# FET.net
KiCad netlist of a schematic drawn in Altium Designer
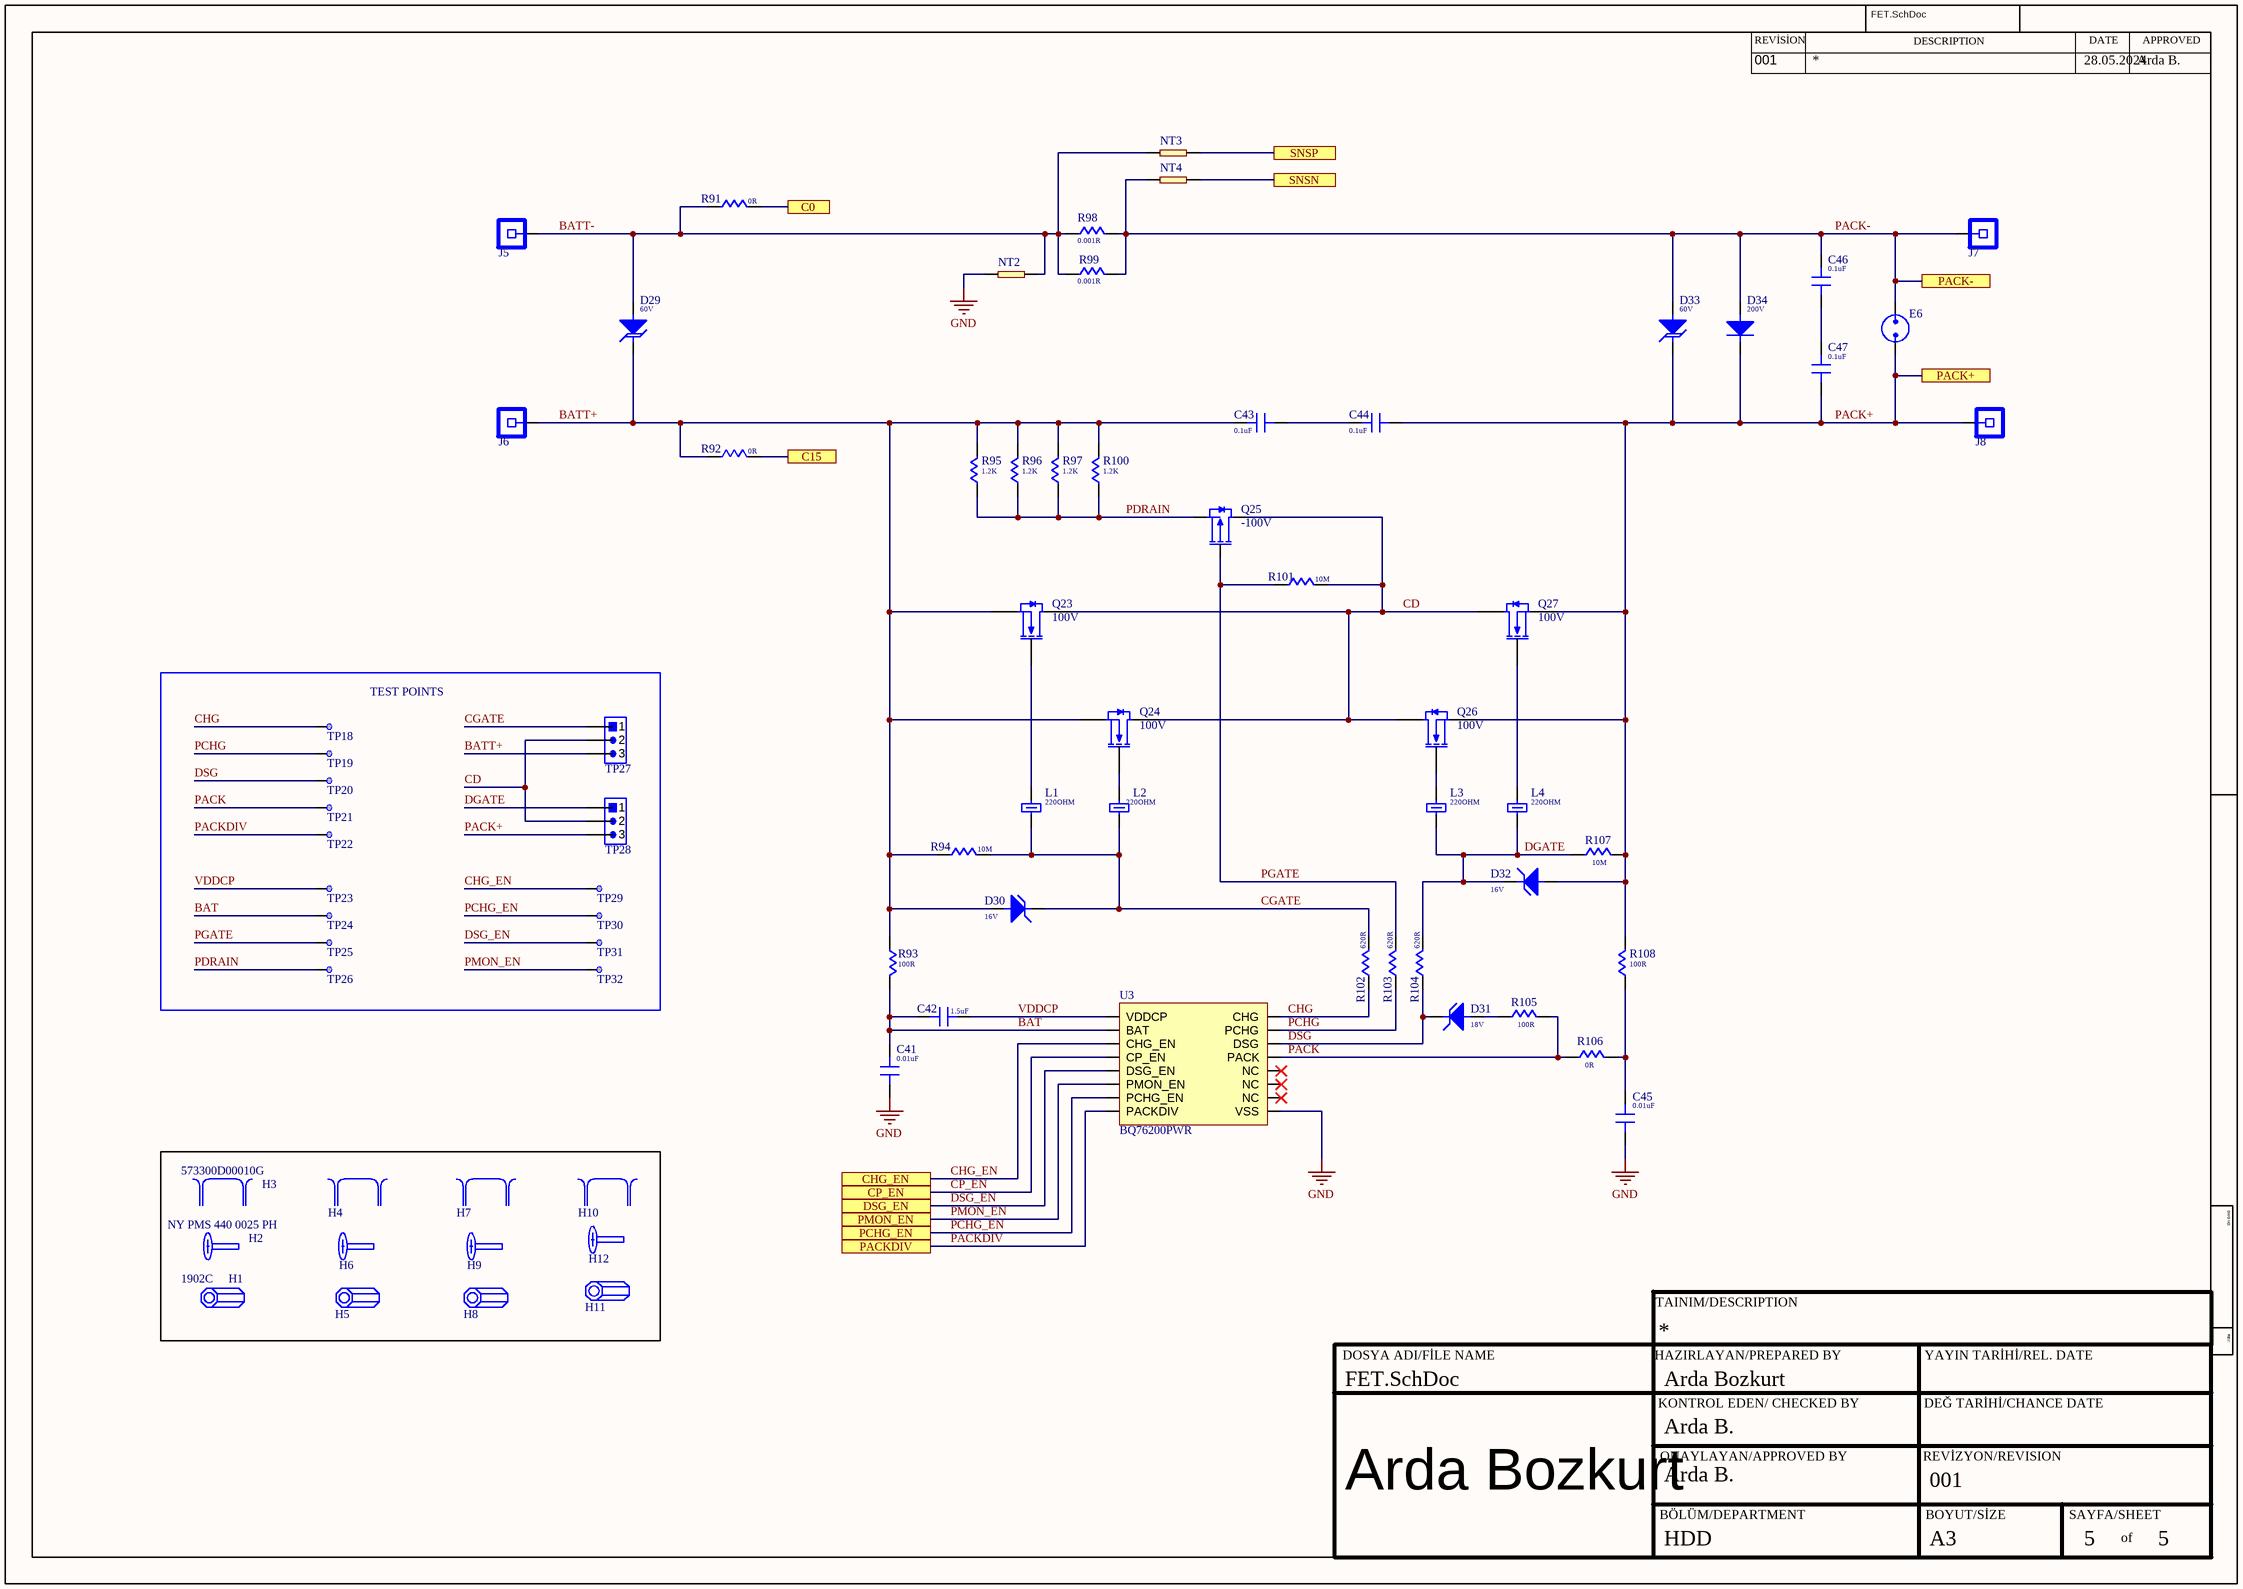
[diagram p0: FET.SchDoc]

(export (version "E")
  (design (tool "Eeschema 10.0.6"))
  (components
    (comp (ref "C41")
      (value "0.01uF")
      (footprint "C_0805")
      (description "Cap Cer 10000PF 100V X7R 0805")
      (fields
        (field (name "MANUFACTURER") "Kyocera AVX")
        (field (name "MANUFACTURER PART NUMBER") "KGM21NR72A103KT")
      )
      (libsource (lib "BMS_Lib") (part "C_0.01uF_0805_100V"))
    )
    (comp (ref "C42")
      (value "1.5uF")
      (footprint "C_0805")
      (description "0805 1.5 uF 25 V ±10% Tolerance X7R SMT Multilayer Ceramic Capacitor")
      (fields
        (field (name "MANUFACTURER") "Murata")
        (field (name "MANUFACTURER PART NUMBER") "GRM21BR71E155KA88L")
      )
      (libsource (lib "BMS_Lib") (part "C_1.5uF_0805_25V"))
    )
    (comp (ref "C43")
      (value "0.1uF")
      (footprint "C_0603")
      (description "Multilayer Ceramic Capacitor, 0.1 uF, 100 V, ± 10%, X7R, 0603 [1608 Metric]")
      (fields
        (field (name "MANUFACTURER") "Murata")
        (field (name "MANUFACTURER PART NUMBER") "GRM188R72A104KA35D")
      )
      (libsource (lib "BMS_Lib") (part "C_0.1uF_0603_100V"))
    )
    (comp (ref "C44")
      (value "0.1uF")
      (footprint "C_0603")
      (description "Multilayer Ceramic Capacitor, 0.1 uF, 100 V, ± 10%, X7R, 0603 [1608 Metric]")
      (fields
        (field (name "MANUFACTURER") "Murata")
        (field (name "MANUFACTURER PART NUMBER") "GRM188R72A104KA35D")
      )
      (libsource (lib "BMS_Lib") (part "C_0.1uF_0603_100V"))
    )
    (comp (ref "C45")
      (value "0.01uF")
      (footprint "C_0805")
      (description "Cap Cer 10000PF 100V X7R 0805")
      (fields
        (field (name "MANUFACTURER") "Kyocera AVX")
        (field (name "MANUFACTURER PART NUMBER") "KGM21NR72A103KT")
      )
      (libsource (lib "BMS_Lib") (part "C_0.01uF_0805_100V"))
    )
    (comp (ref "C46")
      (value "0.1uF")
      (footprint "C_0603")
      (description "Multilayer Ceramic Capacitor, 0.1 uF, 100 V, ± 10%, X7R, 0603 [1608 Metric]")
      (fields
        (field (name "MANUFACTURER") "Murata")
        (field (name "MANUFACTURER PART NUMBER") "GRM188R72A104KA35D")
      )
      (libsource (lib "BMS_Lib") (part "C_0.1uF_0603_100V"))
    )
    (comp (ref "C47")
      (value "0.1uF")
      (footprint "C_0603")
      (description "Multilayer Ceramic Capacitor, 0.1 uF, 100 V, ± 10%, X7R, 0603 [1608 Metric]")
      (fields
        (field (name "MANUFACTURER") "Murata")
        (field (name "MANUFACTURER PART NUMBER") "GRM188R72A104KA35D")
      )
      (libsource (lib "BMS_Lib") (part "C_0.1uF_0603_100V"))
    )
    (comp (ref "D29")
      (value "60V")
      (footprint "D_SMC")
      (description "Diode TVS Single Uni-Dir 6V 1.5KW 2-Pin DO-214AB")
      (fields (field (name "MANUFACTURER") "Littelfuse") (field (name "MANUFACTURER PART NUMBER") "SMCJ6.0A"))
      (libsource (lib "BMS_Lib") (part "D_TVS_60V-SMC"))
    )
    (comp (ref "D30")
      (value "16V")
      (footprint "D_SOD323")
      (description "Zener Diode, 16V, 0.2W, Sod-323 Rohs Compliant: Yes ¦Diodes Inc. MMSZ5246BS-7-F")
      (fields
        (field (name "MANUFACTURER") "Diodes Zetex")
        (field (name "MANUFACTURER PART NUMBER") "MMSZ5246BS-7-F")
      )
      (libsource (lib "BMS_Lib") (part "D_ZENER_16V_SOD323"))
    )
    (comp (ref "D31")
      (value "18V")
      (footprint "D_SOD323")
      (description "Diode Zener Single 18V 5% 200mW Automotive 2-Pin SOD-323 T/R")
      (fields
        (field (name "MANUFACTURER") "Diodes")
        (field (name "MANUFACTURER PART NUMBER") "MMSZ5248BS-7-F")
      )
      (libsource (lib "BMS_Lib") (part "D_ZENER_18V_SOD323"))
    )
    (comp (ref "D32")
      (value "16V")
      (footprint "D_SOD323")
      (description "Zener Diode, 16V, 0.2W, Sod-323 Rohs Compliant: Yes ¦Diodes Inc. MMSZ5246BS-7-F")
      (fields
        (field (name "MANUFACTURER") "Diodes Zetex")
        (field (name "MANUFACTURER PART NUMBER") "MMSZ5246BS-7-F")
      )
      (libsource (lib "BMS_Lib") (part "D_ZENER_16V_SOD323"))
    )
    (comp (ref "D33")
      (value "60V")
      (footprint "D_SMC")
      (description "Diode TVS Single Uni-Dir 6V 1.5KW 2-Pin DO-214AB")
      (fields (field (name "MANUFACTURER") "Littelfuse") (field (name "MANUFACTURER PART NUMBER") "SMCJ6.0A"))
      (libsource (lib "BMS_Lib") (part "D_TVS_60V-SMC"))
    )
    (comp (ref "D34")
      (value "200V")
      (footprint "D_DO214AB")
      (description "Rectifier Diode Switching 200V 3A 20ns 2-Pin SMC T/R / DIODE GEN PURP 200V 3A DO214AB")
      (fields
        (field (name "MANUFACTURER") "Vishay Semiconductors")
        (field (name "MANUFACTURER PART NUMBER") "ES3D-E3/57T")
      )
      (libsource (lib "BMS_Lib") (part "D_GENPURP_200V_DO214AB"))
    )
    (comp (ref "E6")
      (value "SPARKGAP")
      (footprint "SPARK_GARP")
      (description "Spark Gap")
      (libsource (lib "BMS_Lib") (part "E_Spark_Gap"))
    )
    (comp (ref "H1")
      (value "1902C")
      (footprint "HEX_STANDOFF")
      (description "Transistor: 2xN-MOSFET; unipolar; 20V; 1.1A; 0.235ohm; 420mW; -55+150 deg.C; SMD; SC70-6")
      (fields
        (field (name "MANUFACTURER") "Vishay")
        (field (name "MANUFACTURER PART NUMBER") "SI1902CDL-T1-GE3")
      )
      (libsource (lib "BMS_Lib") (part "HEX STANDOFF"))
    )
    (comp (ref "H2")
      (value "NY PMS 440 0025 PH")
      (footprint "PEN")
      (description "Machine Screw Pan Phillips 4-40")
      (fields (field (name "MANUFACTURER") "Building Fasteners"))
      (libsource (lib "BMS_Lib") (part "MACHINE SCREW PAN PHILLIPS 4-40"))
    )
    (comp (ref "H3")
      (value "573300D00010G")
      (footprint "HEATSINK")
      (description "TO-226 Surface Mount 18.00 C/W Thermal Resistance D2 Semiconductor Heat Sink")
      (fields (field (name "MANUFACTURER") "Aavid Thermalloy"))
      (libsource (lib "BMS_Lib") (part "Heatsink"))
    )
    (comp (ref "H4")
      (value "573300D00010G")
      (footprint "HEATSINK")
      (description "TO-226 Surface Mount 18.00 C/W Thermal Resistance D2 Semiconductor Heat Sink")
      (fields (field (name "MANUFACTURER") "Aavid Thermalloy"))
      (libsource (lib "BMS_Lib") (part "Heatsink"))
    )
    (comp (ref "H5")
      (value "1902C")
      (footprint "HEX_STANDOFF")
      (description "Transistor: 2xN-MOSFET; unipolar; 20V; 1.1A; 0.235ohm; 420mW; -55+150 deg.C; SMD; SC70-6")
      (fields
        (field (name "MANUFACTURER") "Vishay")
        (field (name "MANUFACTURER PART NUMBER") "SI1902CDL-T1-GE3")
      )
      (libsource (lib "BMS_Lib") (part "HEX STANDOFF"))
    )
    (comp (ref "H6")
      (value "NY PMS 440 0025 PH")
      (footprint "PEN")
      (description "Machine Screw Pan Phillips 4-40")
      (fields (field (name "MANUFACTURER") "Building Fasteners"))
      (libsource (lib "BMS_Lib") (part "MACHINE SCREW PAN PHILLIPS 4-40"))
    )
    (comp (ref "H7")
      (value "573300D00010G")
      (footprint "HEATSINK")
      (description "TO-226 Surface Mount 18.00 C/W Thermal Resistance D2 Semiconductor Heat Sink")
      (fields (field (name "MANUFACTURER") "Aavid Thermalloy"))
      (libsource (lib "BMS_Lib") (part "Heatsink"))
    )
    (comp (ref "H8")
      (value "1902C")
      (footprint "HEX_STANDOFF")
      (description "Transistor: 2xN-MOSFET; unipolar; 20V; 1.1A; 0.235ohm; 420mW; -55+150 deg.C; SMD; SC70-6")
      (fields
        (field (name "MANUFACTURER") "Vishay")
        (field (name "MANUFACTURER PART NUMBER") "SI1902CDL-T1-GE3")
      )
      (libsource (lib "BMS_Lib") (part "HEX STANDOFF"))
    )
    (comp (ref "H9")
      (value "NY PMS 440 0025 PH")
      (footprint "PEN")
      (description "Machine Screw Pan Phillips 4-40")
      (fields (field (name "MANUFACTURER") "Building Fasteners"))
      (libsource (lib "BMS_Lib") (part "MACHINE SCREW PAN PHILLIPS 4-40"))
    )
    (comp (ref "H10")
      (value "573300D00010G")
      (footprint "HEATSINK")
      (description "TO-226 Surface Mount 18.00 C/W Thermal Resistance D2 Semiconductor Heat Sink")
      (fields (field (name "MANUFACTURER") "Aavid Thermalloy"))
      (libsource (lib "BMS_Lib") (part "Heatsink"))
    )
    (comp (ref "H11")
      (value "1902C")
      (footprint "HEX_STANDOFF")
      (description "Transistor: 2xN-MOSFET; unipolar; 20V; 1.1A; 0.235ohm; 420mW; -55+150 deg.C; SMD; SC70-6")
      (fields
        (field (name "MANUFACTURER") "Vishay")
        (field (name "MANUFACTURER PART NUMBER") "SI1902CDL-T1-GE3")
      )
      (libsource (lib "BMS_Lib") (part "HEX STANDOFF"))
    )
    (comp (ref "H12")
      (value "NY PMS 440 0025 PH")
      (footprint "PEN")
      (description "Machine Screw Pan Phillips 4-40")
      (fields (field (name "MANUFACTURER") "Building Fasteners"))
      (libsource (lib "BMS_Lib") (part "MACHINE SCREW PAN PHILLIPS 4-40"))
    )
    (comp (ref "J5")
      (value "ML4-CY")
      (footprint "CONN_LUG")
      (description "One-hole copper single barrel post lug straight tongue 14 SOL - 4 STR 1/4 (6.4mm) stud hole.")
      (fields (field (name "MANUFACTURER") "Panduit"))
      (libsource (lib "BMS_Lib") (part "CONN_LUG"))
    )
    (comp (ref "J6")
      (value "ML4-CY")
      (footprint "CONN_LUG")
      (description "One-hole copper single barrel post lug straight tongue 14 SOL - 4 STR 1/4 (6.4mm) stud hole.")
      (fields (field (name "MANUFACTURER") "Panduit"))
      (libsource (lib "BMS_Lib") (part "CONN_LUG"))
    )
    (comp (ref "J7")
      (value "ML4-CY")
      (footprint "CONN_LUG")
      (description "One-hole copper single barrel post lug straight tongue 14 SOL - 4 STR 1/4 (6.4mm) stud hole.")
      (fields (field (name "MANUFACTURER") "Panduit"))
      (libsource (lib "") (part "CONN_LUG_1"))
    )
    (comp (ref "J8")
      (value "ML4-CY")
      (footprint "CONN_LUG")
      (description "One-hole copper single barrel post lug straight tongue 14 SOL - 4 STR 1/4 (6.4mm) stud hole.")
      (fields (field (name "MANUFACTURER") "Panduit"))
      (libsource (lib "") (part "CONN_LUG_1"))
    )
    (comp (ref "L1")
      (value "220OHM")
      (footprint "L_0603")
      (description "Ferrite Beads Multi-Layer 220Ohm 25% 100MHz 2.5A 40mOhm DCR 0603 Paper T/R")
      (fields
        (field (name "MANUFACTURER") "Murata")
        (field (name "MANUFACTURER PART NUMBER") "BLM18SG221TN1D")
      )
      (libsource (lib "BMS_Lib") (part "L_FB_220OHM_0603"))
    )
    (comp (ref "L2")
      (value "220OHM")
      (footprint "L_0603")
      (description "Ferrite Beads Multi-Layer 220Ohm 25% 100MHz 2.5A 40mOhm DCR 0603 Paper T/R")
      (fields
        (field (name "MANUFACTURER") "Murata")
        (field (name "MANUFACTURER PART NUMBER") "BLM18SG221TN1D")
      )
      (libsource (lib "BMS_Lib") (part "L_FB_220OHM_0603"))
    )
    (comp (ref "L3")
      (value "220OHM")
      (footprint "L_0603")
      (description "Ferrite Beads Multi-Layer 220Ohm 25% 100MHz 2.5A 40mOhm DCR 0603 Paper T/R")
      (fields
        (field (name "MANUFACTURER") "Murata")
        (field (name "MANUFACTURER PART NUMBER") "BLM18SG221TN1D")
      )
      (libsource (lib "BMS_Lib") (part "L_FB_220OHM_0603"))
    )
    (comp (ref "L4")
      (value "220OHM")
      (footprint "L_0603")
      (description "Ferrite Beads Multi-Layer 220Ohm 25% 100MHz 2.5A 40mOhm DCR 0603 Paper T/R")
      (fields
        (field (name "MANUFACTURER") "Murata")
        (field (name "MANUFACTURER PART NUMBER") "BLM18SG221TN1D")
      )
      (libsource (lib "BMS_Lib") (part "L_FB_220OHM_0603"))
    )
    (comp (ref "NT2")
      (value "NET Tie")
      (footprint "NET_TİE_2")
      (description "Single point connection between nets.")
      (libsource (lib "BMS_Lib") (part "NET_TİE_2"))
    )
    (comp (ref "NT3")
      (value "NET Tie")
      (footprint "NET_TİE_3")
      (description "Single point connection between nets.")
      (libsource (lib "BMS_Lib") (part "NET_TİE_3"))
    )
    (comp (ref "NT4")
      (value "NET Tie")
      (footprint "NET_TİE_3")
      (description "Single point connection between nets.")
      (libsource (lib "BMS_Lib") (part "NET_TİE_3"))
    )
    (comp (ref "Q23")
      (value "CSD19536KTT")
      (footprint "Q_DDPAK")
      (description "100-V, N channel NexFET™ power MOSFET, single D2PAK, 2.4 mOhm 3-DDPAK/TO-263 -55 to 175")
      (fields (field (name "MANUFACTURER") "Texas Instruments") (field (name "VOLTAGE") "100V"))
      (libsource (lib "BMS_Lib") (part "Q_MOSFET_100V_TO363"))
    )
    (comp (ref "Q24")
      (value "CSD19536KTT")
      (footprint "Q_DDPAK")
      (description "100-V, N channel NexFET™ power MOSFET, single D2PAK, 2.4 mOhm 3-DDPAK/TO-263 -55 to 175")
      (fields (field (name "MANUFACTURER") "Texas Instruments") (field (name "VOLTAGE") "100V"))
      (libsource (lib "BMS_Lib") (part "Q_MOSFET_100V_TO363"))
    )
    (comp (ref "Q25")
      (value "ZXMP10A13FTA")
      (footprint "Q_SOT23-3")
      (description "P-Channel 100 V 1 Ohm Surface Mount Enhancement Mode MOSFET - SOT-23")
      (fields (field (name "MANUFACTURER") "Diodes Zetex") (field (name "VOLTAGE RATING (DC)") "-100V"))
      (libsource (lib "BMS_Lib") (part "Q_MOSFET_100V_SOT23-3_1"))
    )
    (comp (ref "Q26")
      (value "CSD19536KTT")
      (footprint "Q_DDPAK")
      (description "100-V, N channel NexFET™ power MOSFET, single D2PAK, 2.4 mOhm 3-DDPAK/TO-263 -55 to 175")
      (fields (field (name "MANUFACTURER") "Texas Instruments") (field (name "VOLTAGE") "100V"))
      (libsource (lib "BMS_Lib") (part "Q_MOSFET_100V_TO363"))
    )
    (comp (ref "Q27")
      (value "CSD19536KTT")
      (footprint "Q_DDPAK")
      (description "100-V, N channel NexFET™ power MOSFET, single D2PAK, 2.4 mOhm 3-DDPAK/TO-263 -55 to 175")
      (fields (field (name "MANUFACTURER") "Texas Instruments") (field (name "VOLTAGE") "100V"))
      (libsource (lib "BMS_Lib") (part "Q_MOSFET_100V_TO363"))
    )
    (comp (ref "R91")
      (value "0R")
      (footprint "R_0603")
      (description "Zero Ohm Resistor, Jumper, 0603 [1608 Metric], Thick Film, 330 mW, 5 A, Surface Mount")
      (fields
        (field (name "MANUFACTURER") "Vishay Dale")
        (field (name "MANUFACTURER PART NUMBER") "CRCW06030000Z0EAHP")
      )
      (libsource (lib "BMS_Lib") (part "R_0OHM_1/10W_0603"))
    )
    (comp (ref "R92")
      (value "0R")
      (footprint "R_0603")
      (description "Zero Ohm Resistor, Jumper, 0603 [1608 Metric], Thick Film, 330 mW, 5 A, Surface Mount")
      (fields
        (field (name "MANUFACTURER") "Vishay Dale")
        (field (name "MANUFACTURER PART NUMBER") "CRCW06030000Z0EAHP")
      )
      (libsource (lib "BMS_Lib") (part "R_0OHM_1/10W_0603"))
    )
    (comp (ref "R93")
      (value "100R")
      (footprint "R_0603")
      (description "SMD Chip Resistor, 100 Ohm, ± 1%, 100 mW, 0603 [1608 Metric], Thick Film, General Purpose")
      (fields
        (field (name "MANUFACTURER") "Vishay Dale")
        (field (name "MANUFACTURER PART NUMBER") "CRCW0603100RFKEA")
      )
      (libsource (lib "BMS_Lib") (part "R_100OHM_%1_1/10W_0603"))
    )
    (comp (ref "R94")
      (value "10M")
      (footprint "R_0603")
      (description "SMD Chip Resistor, 10 MOhm, ± 1%, 100 mW, 0603 [1608 Metric], Thick Film, General Purpose")
      (fields
        (field (name "MANUFACTURER") "Vishay")
        (field (name "MANUFACTURER PART NUMBER") "CRCW060310M0FKEA")
      )
      (libsource (lib "BMS_Lib") (part "R_10M_%1_1/10W_0603"))
    )
    (comp (ref "R95")
      (value "1.2K")
      (footprint "R_2512")
      (description "Res Thick Film 2512 1.2K Ohm 5% 1W ±200ppm/°C Molded SMD SMD Blister T/R")
      (fields
        (field (name "MANUFACTURER") "Vishay")
        (field (name "MANUFACTURER PART NUMBER") "CRCW25121K20JNEG")
      )
      (libsource (lib "BMS_Lib") (part "R_1.2K_%5_1W_2512"))
    )
    (comp (ref "R96")
      (value "1.2K")
      (footprint "R_2512")
      (description "Res Thick Film 2512 1.2K Ohm 5% 1W ±200ppm/°C Molded SMD SMD Blister T/R")
      (fields
        (field (name "MANUFACTURER") "Vishay")
        (field (name "MANUFACTURER PART NUMBER") "CRCW25121K20JNEG")
      )
      (libsource (lib "BMS_Lib") (part "R_1.2K_%5_1W_2512"))
    )
    (comp (ref "R97")
      (value "1.2K")
      (footprint "R_2512")
      (description "Res Thick Film 2512 1.2K Ohm 5% 1W ±200ppm/°C Molded SMD SMD Blister T/R")
      (fields
        (field (name "MANUFACTURER") "Vishay")
        (field (name "MANUFACTURER PART NUMBER") "CRCW25121K20JNEG")
      )
      (libsource (lib "BMS_Lib") (part "R_1.2K_%5_1W_2512"))
    )
    (comp (ref "R98")
      (value "0.001R")
      (footprint "R_2010")
      (description "Res Metal Foil 2010 0.001 Ohm 1% 1.5W ±50ppm/°C Molded SMD SMD Plastic T/R")
      (fields
        (field (name "MANUFACTURER") "Stackpole Electronics")
        (field (name "MANUFACTURER PART NUMBER") "CSNL2010FT1L00")
      )
      (libsource (lib "BMS_Lib") (part "R_0.001OHM_%1_1.5W_2010"))
    )
    (comp (ref "R99")
      (value "0.001R")
      (footprint "R_2010")
      (description "Res Metal Foil 2010 0.001 Ohm 1% 1.5W ±50ppm/°C Molded SMD SMD Plastic T/R")
      (fields
        (field (name "MANUFACTURER") "Stackpole Electronics")
        (field (name "MANUFACTURER PART NUMBER") "CSNL2010FT1L00")
      )
      (libsource (lib "BMS_Lib") (part "R_0.001OHM_%1_1.5W_2010"))
    )
    (comp (ref "R100")
      (value "1.2K")
      (footprint "R_2512")
      (description "Res Thick Film 2512 1.2K Ohm 5% 1W ±200ppm/°C Molded SMD SMD Blister T/R")
      (fields
        (field (name "MANUFACTURER") "Vishay")
        (field (name "MANUFACTURER PART NUMBER") "CRCW25121K20JNEG")
      )
      (libsource (lib "BMS_Lib") (part "R_1.2K_%5_1W_2512"))
    )
    (comp (ref "R101")
      (value "10M")
      (footprint "R_0603")
      (description "SMD Chip Resistor, 10 MOhm, ± 1%, 100 mW, 0603 [1608 Metric], Thick Film, General Purpose")
      (fields
        (field (name "MANUFACTURER") "Vishay")
        (field (name "MANUFACTURER PART NUMBER") "CRCW060310M0FKEA")
      )
      (libsource (lib "BMS_Lib") (part "R_10M_%1_1/10W_0603"))
    )
    (comp (ref "R102")
      (value "620R")
      (footprint "R_0603")
      (description "SMD Chip Resistor, 620 Ohm, ± 5%, 100 mW, 0603 [1608 Metric], Thick Film, General Purpose")
      (fields
        (field (name "MANUFACTURER") "Vishay Dale")
        (field (name "MANUFACTURER PART NUMBER") "CRCW0603620RJNEA")
      )
      (libsource (lib "BMS_Lib") (part "R_620OHM_%5_1/10W_0603"))
    )
    (comp (ref "R103")
      (value "620R")
      (footprint "R_0603")
      (description "SMD Chip Resistor, 620 Ohm, ± 5%, 100 mW, 0603 [1608 Metric], Thick Film, General Purpose")
      (fields
        (field (name "MANUFACTURER") "Vishay Dale")
        (field (name "MANUFACTURER PART NUMBER") "CRCW0603620RJNEA")
      )
      (libsource (lib "BMS_Lib") (part "R_620OHM_%5_1/10W_0603"))
    )
    (comp (ref "R104")
      (value "620R")
      (footprint "R_0603")
      (description "SMD Chip Resistor, 620 Ohm, ± 5%, 100 mW, 0603 [1608 Metric], Thick Film, General Purpose")
      (fields
        (field (name "MANUFACTURER") "Vishay Dale")
        (field (name "MANUFACTURER PART NUMBER") "CRCW0603620RJNEA")
      )
      (libsource (lib "BMS_Lib") (part "R_620OHM_%5_1/10W_0603"))
    )
    (comp (ref "R105")
      (value "100R")
      (footprint "R_0603")
      (description "SMD Chip Resistor, 100 Ohm, ± 5%, 100 mW, 0603 [1608 Metric], Thick Film, General Purpose")
      (fields
        (field (name "MANUFACTURER") "Vishay Dale")
        (field (name "MANUFACTURER PART NUMBER") "CRCW0603100RJNEA")
      )
      (libsource (lib "BMS_Lib") (part "R_100OHM_%5_1/10W_0603"))
    )
    (comp (ref "R106")
      (value "0R")
      (footprint "R_0603")
      (description "Zero Ohm Resistor, Jumper, 0603 [1608 Metric], Thick Film, 330 mW, 5 A, Surface Mount")
      (fields
        (field (name "MANUFACTURER") "Vishay Dale")
        (field (name "MANUFACTURER PART NUMBER") "CRCW06030000Z0EAHP")
      )
      (libsource (lib "BMS_Lib") (part "R_0OHM_1/10W_0603"))
    )
    (comp (ref "R107")
      (value "10M")
      (footprint "R_0603")
      (description "SMD Chip Resistor, 10 MOhm, ± 1%, 100 mW, 0603 [1608 Metric], Thick Film, General Purpose")
      (fields
        (field (name "MANUFACTURER") "Vishay")
        (field (name "MANUFACTURER PART NUMBER") "CRCW060310M0FKEA")
      )
      (libsource (lib "BMS_Lib") (part "R_10M_%1_1/10W_0603"))
    )
    (comp (ref "R108")
      (value "100R")
      (footprint "R_0603")
      (description "SMD Chip Resistor, 100 Ohm, ± 1%, 100 mW, 0603 [1608 Metric], Thick Film, General Purpose")
      (fields
        (field (name "MANUFACTURER") "Vishay Dale")
        (field (name "MANUFACTURER PART NUMBER") "CRCW0603100RFKEA")
      )
      (libsource (lib "BMS_Lib") (part "R_100OHM_%1_1/10W_0603"))
    )
    (comp (ref "TP18")
      (value "5011")
      (footprint "TP_VİA")
      (fields (field (name "MANUFACTURER") "Keystone Electronics"))
      (libsource (lib "BMS_Lib") (part "TP_PC_TEST_POİNT"))
    )
    (comp (ref "TP19")
      (value "5011")
      (footprint "TP_VİA")
      (fields (field (name "MANUFACTURER") "Keystone Electronics"))
      (libsource (lib "BMS_Lib") (part "TP_PC_TEST_POİNT"))
    )
    (comp (ref "TP20")
      (value "5011")
      (footprint "TP_VİA")
      (fields (field (name "MANUFACTURER") "Keystone Electronics"))
      (libsource (lib "BMS_Lib") (part "TP_PC_TEST_POİNT"))
    )
    (comp (ref "TP21")
      (value "5011")
      (footprint "TP_VİA")
      (fields (field (name "MANUFACTURER") "Keystone Electronics"))
      (libsource (lib "BMS_Lib") (part "TP_PC_TEST_POİNT"))
    )
    (comp (ref "TP22")
      (value "5011")
      (footprint "TP_VİA")
      (fields (field (name "MANUFACTURER") "Keystone Electronics"))
      (libsource (lib "BMS_Lib") (part "TP_PC_TEST_POİNT"))
    )
    (comp (ref "TP23")
      (value "5011")
      (footprint "TP_VİA")
      (fields (field (name "MANUFACTURER") "Keystone Electronics"))
      (libsource (lib "BMS_Lib") (part "TP_PC_TEST_POİNT"))
    )
    (comp (ref "TP24")
      (value "5011")
      (footprint "TP_VİA")
      (fields (field (name "MANUFACTURER") "Keystone Electronics"))
      (libsource (lib "BMS_Lib") (part "TP_PC_TEST_POİNT"))
    )
    (comp (ref "TP25")
      (value "5011")
      (footprint "TP_VİA")
      (fields (field (name "MANUFACTURER") "Keystone Electronics"))
      (libsource (lib "BMS_Lib") (part "TP_PC_TEST_POİNT"))
    )
    (comp (ref "TP26")
      (value "5011")
      (footprint "TP_VİA")
      (fields (field (name "MANUFACTURER") "Keystone Electronics"))
      (libsource (lib "BMS_Lib") (part "TP_PC_TEST_POİNT"))
    )
    (comp (ref "TP27")
      (value "PEC03SAAN")
      (footprint "TP_3POS")
      (description "PEC Series Single Row 3 Position 2.54 mm Straight Breakaway Header")
      (fields (field (name "MANUFACTURER") "Sullins"))
      (libsource (lib "BMS_Lib") (part "TP_CONN_3POS_2.54MM"))
    )
    (comp (ref "TP28")
      (value "PEC03SAAN")
      (footprint "TP_3POS")
      (description "PEC Series Single Row 3 Position 2.54 mm Straight Breakaway Header")
      (fields (field (name "MANUFACTURER") "Sullins"))
      (libsource (lib "BMS_Lib") (part "TP_CONN_3POS_2.54MM"))
    )
    (comp (ref "TP29")
      (value "5011")
      (footprint "TP_VİA")
      (fields (field (name "MANUFACTURER") "Keystone Electronics"))
      (libsource (lib "BMS_Lib") (part "TP_PC_TEST_POİNT"))
    )
    (comp (ref "TP30")
      (value "5011")
      (footprint "TP_VİA")
      (fields (field (name "MANUFACTURER") "Keystone Electronics"))
      (libsource (lib "BMS_Lib") (part "TP_PC_TEST_POİNT"))
    )
    (comp (ref "TP31")
      (value "5011")
      (footprint "TP_VİA")
      (fields (field (name "MANUFACTURER") "Keystone Electronics"))
      (libsource (lib "BMS_Lib") (part "TP_PC_TEST_POİNT"))
    )
    (comp (ref "TP32")
      (value "5011")
      (footprint "TP_VİA")
      (fields (field (name "MANUFACTURER") "Keystone Electronics"))
      (libsource (lib "BMS_Lib") (part "TP_PC_TEST_POİNT"))
    )
    (comp (ref "U3")
      (value "BQ76200PWR")
      (footprint "16TSSOP")
      (description "HIGH-SIDEN-CHFETDRVR16TSSOP")
      (fields (field (name "MANUFACTURER") "Texas Instruments"))
      (libsource (lib "BMS_Lib") (part "FET_DRİVER_16TSTOP"))
    )
  )
  (nets
    (net (code "1") (name "/BAT") (class "Default")
      (node (ref "C41") (pin "2") (pinfunction "2_2") (pintype "passive"))
      (node (ref "C42") (pin "1") (pinfunction "1_1") (pintype "passive"))
      (node (ref "R93") (pin "2") (pinfunction "2_2") (pintype "passive"))
      (node (ref "TP24") (pin "1") (pinfunction "1_1") (pintype "passive"))
      (node (ref "U3") (pin "2") (pinfunction "BAT_2") (pintype "passive"))
    )
    (net (code "2") (name "/BATT+") (class "Default")
      (node (ref "C43") (pin "2") (pinfunction "2_2") (pintype "passive"))
      (node (ref "D29") (pin "1") (pinfunction "1_1") (pintype "passive"))
      (node (ref "D30") (pin "2") (pinfunction "2_2") (pintype "passive"))
      (node (ref "J6") (pin "1") (pinfunction "1_1") (pintype "passive"))
      (node (ref "Q23") (pin "3") (pinfunction "S_3") (pintype "passive"))
      (node (ref "Q24") (pin "3") (pinfunction "S_3") (pintype "passive"))
      (node (ref "R100") (pin "2") (pinfunction "2_2") (pintype "passive"))
      (node (ref "R92") (pin "1") (pinfunction "1_1") (pintype "passive"))
      (node (ref "R93") (pin "1") (pinfunction "1_1") (pintype "passive"))
      (node (ref "R94") (pin "1") (pinfunction "1_1") (pintype "passive"))
      (node (ref "R95") (pin "2") (pinfunction "2_2") (pintype "passive"))
      (node (ref "R96") (pin "2") (pinfunction "2_2") (pintype "passive"))
      (node (ref "R97") (pin "2") (pinfunction "2_2") (pintype "passive"))
      (node (ref "TP27") (pin "3") (pinfunction "3_3") (pintype "passive"))
    )
    (net (code "3") (name "/BATT-") (class "Default")
      (node (ref "D29") (pin "2") (pinfunction "2_2") (pintype "passive"))
      (node (ref "J5") (pin "1") (pinfunction "1_1") (pintype "passive"))
      (node (ref "NT2") (pin "2") (pinfunction "2_2") (pintype "passive"))
      (node (ref "NT3") (pin "1") (pinfunction "1_1") (pintype "passive"))
      (node (ref "R91") (pin "1") (pinfunction "1_1") (pintype "passive"))
      (node (ref "R98") (pin "1") (pinfunction "1_1") (pintype "passive"))
      (node (ref "R99") (pin "1") (pinfunction "1_1") (pintype "passive"))
    )
    (net (code "4") (name "/C0") (class "Default")
      (node (ref "R91") (pin "2") (pinfunction "2_2") (pintype "passive"))
    )
    (net (code "5") (name "/C15") (class "Default")
      (node (ref "R92") (pin "2") (pinfunction "2_2") (pintype "passive"))
    )
    (net (code "6") (name "/CD") (class "Default")
      (node (ref "Q23") (pin "2") (pinfunction "D_2") (pintype "passive"))
      (node (ref "Q24") (pin "2") (pinfunction "D_2") (pintype "passive"))
      (node (ref "Q25") (pin "2") (pinfunction "S_2") (pintype "passive"))
      (node (ref "Q26") (pin "2") (pinfunction "D_2") (pintype "passive"))
      (node (ref "Q27") (pin "2") (pinfunction "D_2") (pintype "passive"))
      (node (ref "R101") (pin "2") (pinfunction "2_2") (pintype "passive"))
      (node (ref "TP27") (pin "2") (pinfunction "2_2") (pintype "passive"))
      (node (ref "TP28") (pin "2") (pinfunction "2_2") (pintype "passive"))
    )
    (net (code "7") (name "/CGATE") (class "Default")
      (node (ref "D30") (pin "1") (pinfunction "1_1") (pintype "passive"))
      (node (ref "L1") (pin "1") (pinfunction "1_1") (pintype "passive"))
      (node (ref "L2") (pin "1") (pinfunction "1_1") (pintype "passive"))
      (node (ref "R102") (pin "2") (pinfunction "2_2") (pintype "passive"))
      (node (ref "R94") (pin "2") (pinfunction "2_2") (pintype "passive"))
      (node (ref "TP27") (pin "1") (pinfunction "1_1") (pintype "passive"))
    )
    (net (code "8") (name "/CHG") (class "Default")
      (node (ref "R102") (pin "1") (pinfunction "1_1") (pintype "passive"))
      (node (ref "TP18") (pin "1") (pinfunction "1_1") (pintype "passive"))
      (node (ref "U3") (pin "16") (pinfunction "CHG_16") (pintype "passive"))
    )
    (net (code "9") (name "/CHG_EN") (class "Default")
      (node (ref "TP29") (pin "1") (pinfunction "1_1") (pintype "passive"))
      (node (ref "U3") (pin "4") (pinfunction "CHG_EN_4") (pintype "passive"))
    )
    (net (code "10") (name "/CP_EN") (class "Default")
      (node (ref "U3") (pin "5") (pinfunction "CP_EN_5") (pintype "passive"))
    )
    (net (code "11") (name "/DGATE") (class "Default")
      (node (ref "D32") (pin "1") (pinfunction "1_1") (pintype "passive"))
      (node (ref "L3") (pin "1") (pinfunction "1_1") (pintype "passive"))
      (node (ref "L4") (pin "1") (pinfunction "1_1") (pintype "passive"))
      (node (ref "R104") (pin "2") (pinfunction "2_2") (pintype "passive"))
      (node (ref "R107") (pin "1") (pinfunction "1_1") (pintype "passive"))
      (node (ref "TP28") (pin "1") (pinfunction "1_1") (pintype "passive"))
    )
    (net (code "12") (name "/DSG") (class "Default")
      (node (ref "D31") (pin "1") (pinfunction "1_1") (pintype "passive"))
      (node (ref "R104") (pin "1") (pinfunction "1_1") (pintype "passive"))
      (node (ref "TP20") (pin "1") (pinfunction "1_1") (pintype "passive"))
      (node (ref "U3") (pin "12") (pinfunction "DSG_12") (pintype "passive"))
    )
    (net (code "13") (name "/DSG_EN") (class "Default")
      (node (ref "TP31") (pin "1") (pinfunction "1_1") (pintype "passive"))
      (node (ref "U3") (pin "6") (pinfunction "DSG_EN_6") (pintype "passive"))
    )
    (net (code "14") (name "/PACK") (class "Default")
      (node (ref "R105") (pin "2") (pinfunction "2_2") (pintype "passive"))
      (node (ref "R106") (pin "1") (pinfunction "1_1") (pintype "passive"))
      (node (ref "TP21") (pin "1") (pinfunction "1_1") (pintype "passive"))
      (node (ref "U3") (pin "11") (pinfunction "PACK_11") (pintype "passive"))
    )
    (net (code "15") (name "/PACK+") (class "Default")
      (node (ref "C44") (pin "1") (pinfunction "1_1") (pintype "passive"))
      (node (ref "C47") (pin "1") (pinfunction "1_1") (pintype "passive"))
      (node (ref "D32") (pin "2") (pinfunction "2_2") (pintype "passive"))
      (node (ref "D33") (pin "1") (pinfunction "1_1") (pintype "passive"))
      (node (ref "D34") (pin "1") (pinfunction "1_1") (pintype "passive"))
      (node (ref "E6") (pin "1") (pinfunction "1_1") (pintype "passive"))
      (node (ref "J8") (pin "1") (pinfunction "1_1") (pintype "passive"))
      (node (ref "Q26") (pin "3") (pinfunction "S_3") (pintype "passive"))
      (node (ref "Q27") (pin "3") (pinfunction "S_3") (pintype "passive"))
      (node (ref "R107") (pin "2") (pinfunction "2_2") (pintype "passive"))
      (node (ref "R108") (pin "2") (pinfunction "2_2") (pintype "passive"))
      (node (ref "TP28") (pin "3") (pinfunction "3_3") (pintype "passive"))
    )
    (net (code "16") (name "/PACK-") (class "Default")
      (node (ref "C46") (pin "2") (pinfunction "2_2") (pintype "passive"))
      (node (ref "D33") (pin "2") (pinfunction "2_2") (pintype "passive"))
      (node (ref "D34") (pin "2") (pinfunction "2_2") (pintype "passive"))
      (node (ref "E6") (pin "2") (pinfunction "2_2") (pintype "passive"))
      (node (ref "J7") (pin "1") (pinfunction "1_1") (pintype "passive"))
      (node (ref "NT4") (pin "1") (pinfunction "1_1") (pintype "passive"))
      (node (ref "R98") (pin "2") (pinfunction "2_2") (pintype "passive"))
      (node (ref "R99") (pin "2") (pinfunction "2_2") (pintype "passive"))
    )
    (net (code "17") (name "/PACKDIV") (class "Default")
      (node (ref "TP22") (pin "1") (pinfunction "1_1") (pintype "passive"))
      (node (ref "U3") (pin "10") (pinfunction "PACKDIV_10") (pintype "passive"))
    )
    (net (code "18") (name "/PCHG") (class "Default")
      (node (ref "R103") (pin "1") (pinfunction "1_1") (pintype "passive"))
      (node (ref "TP19") (pin "1") (pinfunction "1_1") (pintype "passive"))
      (node (ref "U3") (pin "14") (pinfunction "PCHG_14") (pintype "passive"))
    )
    (net (code "19") (name "/PCHG_EN") (class "Default")
      (node (ref "TP30") (pin "1") (pinfunction "1_1") (pintype "passive"))
      (node (ref "U3") (pin "8") (pinfunction "PCHG_EN_8") (pintype "passive"))
    )
    (net (code "20") (name "/PDRAIN") (class "Default")
      (node (ref "Q25") (pin "3") (pinfunction "D_3") (pintype "passive"))
      (node (ref "R100") (pin "1") (pinfunction "1_1") (pintype "passive"))
      (node (ref "R95") (pin "1") (pinfunction "1_1") (pintype "passive"))
      (node (ref "R96") (pin "1") (pinfunction "1_1") (pintype "passive"))
      (node (ref "R97") (pin "1") (pinfunction "1_1") (pintype "passive"))
      (node (ref "TP26") (pin "1") (pinfunction "1_1") (pintype "passive"))
    )
    (net (code "21") (name "/PGATE") (class "Default")
      (node (ref "Q25") (pin "1") (pinfunction "G_1") (pintype "passive"))
      (node (ref "R101") (pin "1") (pinfunction "1_1") (pintype "passive"))
      (node (ref "R103") (pin "2") (pinfunction "2_2") (pintype "passive"))
      (node (ref "TP25") (pin "1") (pinfunction "1_1") (pintype "passive"))
    )
    (net (code "22") (name "/PMON_EN") (class "Default")
      (node (ref "TP32") (pin "1") (pinfunction "1_1") (pintype "passive"))
      (node (ref "U3") (pin "7") (pinfunction "PMON_EN_7") (pintype "passive"))
    )
    (net (code "23") (name "/SNSN") (class "Default")
      (node (ref "NT4") (pin "2") (pinfunction "2_2") (pintype "passive"))
    )
    (net (code "24") (name "/SNSP") (class "Default")
      (node (ref "NT3") (pin "2") (pinfunction "2_2") (pintype "passive"))
    )
    (net (code "25") (name "/VDDCP") (class "Default")
      (node (ref "C42") (pin "2") (pinfunction "2_2") (pintype "passive"))
      (node (ref "TP23") (pin "1") (pinfunction "1_1") (pintype "passive"))
      (node (ref "U3") (pin "1") (pinfunction "VDDCP_1") (pintype "passive"))
    )
    (net (code "26") (name "GND") (class "Default")
      (node (ref "C41") (pin "1") (pinfunction "1_1") (pintype "passive"))
      (node (ref "C45") (pin "1") (pinfunction "1_1") (pintype "passive"))
      (node (ref "NT2") (pin "1") (pinfunction "1_1") (pintype "passive"))
      (node (ref "U3") (pin "9") (pinfunction "VSS_9") (pintype "passive"))
    )
    (net (code "27") (name "Net-(C43-Pad1)") (class "Default")
      (node (ref "C43") (pin "1") (pinfunction "1_1") (pintype "passive"))
      (node (ref "C44") (pin "2") (pinfunction "2_2") (pintype "passive"))
    )
    (net (code "28") (name "Net-(C45-Pad2)") (class "Default")
      (node (ref "C45") (pin "2") (pinfunction "2_2") (pintype "passive"))
      (node (ref "R106") (pin "2") (pinfunction "2_2") (pintype "passive"))
      (node (ref "R108") (pin "1") (pinfunction "1_1") (pintype "passive"))
    )
    (net (code "29") (name "Net-(C46-Pad1)") (class "Default")
      (node (ref "C46") (pin "1") (pinfunction "1_1") (pintype "passive"))
      (node (ref "C47") (pin "2") (pinfunction "2_2") (pintype "passive"))
    )
    (net (code "30") (name "Net-(D31-Pad2)") (class "Default")
      (node (ref "D31") (pin "2") (pinfunction "2_2") (pintype "passive"))
      (node (ref "R105") (pin "1") (pinfunction "1_1") (pintype "passive"))
    )
    (net (code "31") (name "Net-(Q23-G)") (class "Default")
      (node (ref "L1") (pin "2") (pinfunction "2_2") (pintype "passive"))
      (node (ref "Q23") (pin "1") (pinfunction "G_1") (pintype "passive"))
    )
    (net (code "32") (name "Net-(Q24-G)") (class "Default")
      (node (ref "L2") (pin "2") (pinfunction "2_2") (pintype "passive"))
      (node (ref "Q24") (pin "1") (pinfunction "G_1") (pintype "passive"))
    )
    (net (code "33") (name "Net-(Q26-G)") (class "Default")
      (node (ref "L3") (pin "2") (pinfunction "2_2") (pintype "passive"))
      (node (ref "Q26") (pin "1") (pinfunction "G_1") (pintype "passive"))
    )
    (net (code "34") (name "Net-(Q27-G)") (class "Default")
      (node (ref "L4") (pin "2") (pinfunction "2_2") (pintype "passive"))
      (node (ref "Q27") (pin "1") (pinfunction "G_1") (pintype "passive"))
    )
    (net (code "35") (name "unconnected-(U3-NC-Pad3)") (class "Default")
      (node (ref "U3") (pin "3") (pinfunction "NC_3") (pintype "passive+no_connect"))
    )
    (net (code "36") (name "unconnected-(U3-NC-Pad13)") (class "Default")
      (node (ref "U3") (pin "13") (pinfunction "NC_13") (pintype "passive+no_connect"))
    )
    (net (code "37") (name "unconnected-(U3-NC-Pad15)") (class "Default")
      (node (ref "U3") (pin "15") (pinfunction "NC_15") (pintype "passive+no_connect"))
    )
  )
)
